# Hbridge.net
KiCad netlist of a schematic drawn in Altium Designer
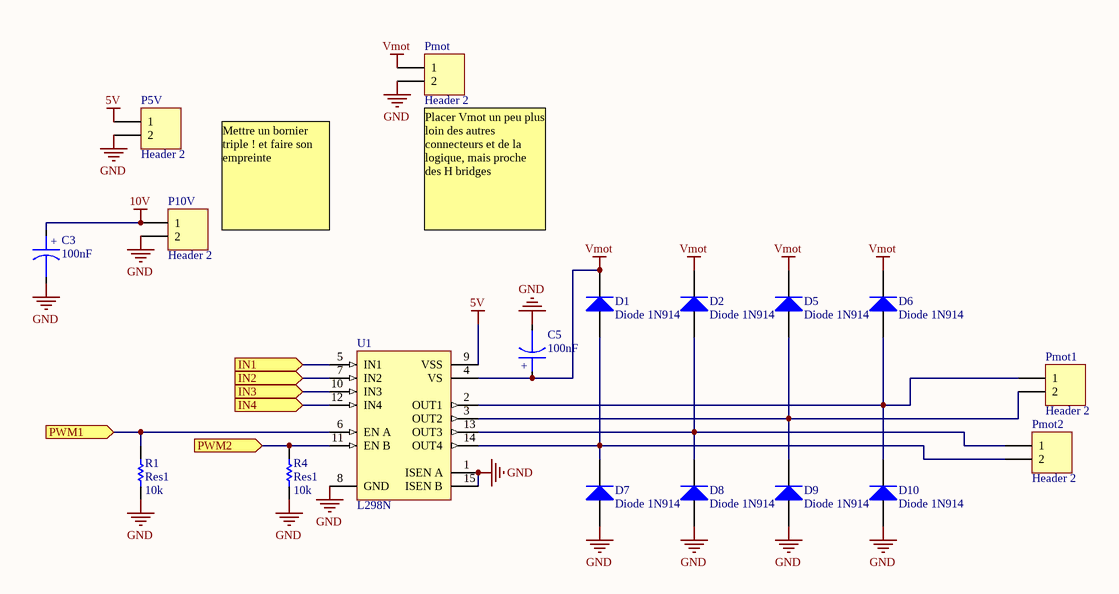
[diagram p0: Hbridge.SchDoc]

(export (version "E")
  (design (tool "Eeschema 10.0.6"))
  (components
    (comp (ref "C3")
      (value "100nF")
      (footprint "RB.1/.3")
      (description "Polarized Capacitor")
      (fields (field (name "Comment") "CAP Pol"))
      (libsource (lib "7Robot") (part "CAP Pol"))
    )
    (comp (ref "C5")
      (value "100nF")
      (footprint "RB.2/.4")
      (description "Polarized Capacitor")
      (fields (field (name "Comment") "CAP Pol"))
      (libsource (lib "7Robot") (part "CAP Pol"))
    )
    (comp (ref "D1")
      (value "Diode 1N914")
      (footprint "DO-35")
      (description "High Conductance Fast Diode")
      (fields (field (name "PUBLISHER") "Altium Limited"))
      (libsource (lib "Miscellaneous Devices") (part "Diode 1N914"))
    )
    (comp (ref "D2")
      (value "Diode 1N914")
      (footprint "DO-35")
      (description "High Conductance Fast Diode")
      (fields (field (name "PUBLISHER") "Altium Limited"))
      (libsource (lib "Miscellaneous Devices") (part "Diode 1N914"))
    )
    (comp (ref "D5")
      (value "Diode 1N914")
      (footprint "DO-35")
      (description "High Conductance Fast Diode")
      (fields (field (name "PUBLISHER") "Altium Limited"))
      (libsource (lib "Miscellaneous Devices") (part "Diode 1N914"))
    )
    (comp (ref "D6")
      (value "Diode 1N914")
      (footprint "DO-35")
      (description "High Conductance Fast Diode")
      (fields (field (name "PUBLISHER") "Altium Limited"))
      (libsource (lib "Miscellaneous Devices") (part "Diode 1N914"))
    )
    (comp (ref "D7")
      (value "Diode 1N914")
      (footprint "DO-35")
      (description "High Conductance Fast Diode")
      (fields (field (name "PUBLISHER") "Altium Limited"))
      (libsource (lib "Miscellaneous Devices") (part "Diode 1N914"))
    )
    (comp (ref "D8")
      (value "Diode 1N914")
      (footprint "DO-35")
      (description "High Conductance Fast Diode")
      (fields (field (name "PUBLISHER") "Altium Limited"))
      (libsource (lib "Miscellaneous Devices") (part "Diode 1N914"))
    )
    (comp (ref "D9")
      (value "Diode 1N914")
      (footprint "DO-35")
      (description "High Conductance Fast Diode")
      (fields (field (name "PUBLISHER") "Altium Limited"))
      (libsource (lib "Miscellaneous Devices") (part "Diode 1N914"))
    )
    (comp (ref "D10")
      (value "Diode 1N914")
      (footprint "DO-35")
      (description "High Conductance Fast Diode")
      (fields (field (name "PUBLISHER") "Altium Limited"))
      (libsource (lib "Miscellaneous Devices") (part "Diode 1N914"))
    )
    (comp (ref "P5V")
      (value "Header 2")
      (footprint "Bornier male coude 2 voies")
      (description "Header, 2-Pin")
      (fields (field (name "PUBLISHER") "Altium Limited"))
      (libsource (lib "7Robot") (part "Header 2"))
    )
    (comp (ref "P10V")
      (value "Header 2")
      (footprint "Bornier male coude 2 voies")
      (description "Header, 2-Pin")
      (fields (field (name "PUBLISHER") "Altium Limited"))
      (libsource (lib "7Robot") (part "Header 2"))
    )
    (comp (ref "Pmot")
      (value "Header 2")
      (footprint "Bornier male coude 2 voies")
      (description "Header, 2-Pin")
      (fields (field (name "PUBLISHER") "Altium Limited"))
      (libsource (lib "7Robot") (part "Header 2"))
    )
    (comp (ref "Pmot1")
      (value "Header 2")
      (footprint "TERM2W-3.5")
      (description "Header, 2-Pin")
      (fields (field (name "PUBLISHER") "Altium Limited"))
      (libsource (lib "7Robot") (part "Header 2"))
    )
    (comp (ref "Pmot2")
      (value "Header 2")
      (footprint "TERM2W-3.5")
      (description "Header, 2-Pin")
      (fields (field (name "PUBLISHER") "Altium Limited"))
      (libsource (lib "7Robot") (part "Header 2"))
    )
    (comp (ref "R1")
      (value "Res1")
      (footprint "AXIAL-0.3")
      (description "Resistor")
      (fields (field (name "ALTIUM_VALUE") "10k") (field (name "PUBLISHER") "Altium Limited"))
      (libsource (lib "Miscellaneous Devices") (part "Res1"))
    )
    (comp (ref "R4")
      (value "Res1")
      (footprint "AXIAL-0.3")
      (description "Resistor")
      (fields (field (name "ALTIUM_VALUE") "10k") (field (name "PUBLISHER") "Altium Limited"))
      (libsource (lib "Miscellaneous Devices") (part "Res1"))
    )
    (comp (ref "U1")
      (value "L298N")
      (footprint "Multiwatt15V")
      (description "Dual Full Bridge Driver")
      (fields (field (name "PUBLISHER") "Altium Limited"))
      (libsource (lib "ST Interface DC Motor Controller") (part "L298N"))
    )
  )
  (nets
    (net (code "1") (name "/IN1") (class "Default")
      (node (ref "U1") (pin "5") (pinfunction "IN1_5") (pintype "input"))
    )
    (net (code "2") (name "/IN2") (class "Default")
      (node (ref "U1") (pin "7") (pinfunction "IN2_7") (pintype "input"))
    )
    (net (code "3") (name "/IN3") (class "Default")
      (node (ref "U1") (pin "10") (pinfunction "IN3_10") (pintype "input"))
    )
    (net (code "4") (name "/IN4") (class "Default")
      (node (ref "U1") (pin "12") (pinfunction "IN4_12") (pintype "input"))
    )
    (net (code "5") (name "/PWM1") (class "Default")
      (node (ref "R1") (pin "2") (pinfunction "2_2") (pintype "passive"))
      (node (ref "U1") (pin "6") (pinfunction "EN_A_6") (pintype "input"))
    )
    (net (code "6") (name "/PWM2") (class "Default")
      (node (ref "R4") (pin "2") (pinfunction "2_2") (pintype "passive"))
      (node (ref "U1") (pin "11") (pinfunction "EN_B_11") (pintype "input"))
    )
    (net (code "7") (name "5V") (class "Default")
      (node (ref "P5V") (pin "1") (pinfunction "1_1") (pintype "passive"))
      (node (ref "U1") (pin "9") (pinfunction "VSS_9") (pintype "power_in"))
    )
    (net (code "8") (name "10V") (class "Default")
      (node (ref "C3") (pin "1") (pinfunction "1_1") (pintype "passive"))
      (node (ref "P10V") (pin "1") (pinfunction "1_1") (pintype "passive"))
    )
    (net (code "9") (name "GND") (class "Default")
      (node (ref "C3") (pin "2") (pinfunction "2_2") (pintype "passive"))
      (node (ref "C5") (pin "2") (pinfunction "2_2") (pintype "passive"))
      (node (ref "D10") (pin "1") (pinfunction "A_1") (pintype "passive"))
      (node (ref "D7") (pin "1") (pinfunction "A_1") (pintype "passive"))
      (node (ref "D8") (pin "1") (pinfunction "A_1") (pintype "passive"))
      (node (ref "D9") (pin "1") (pinfunction "A_1") (pintype "passive"))
      (node (ref "P10V") (pin "2") (pinfunction "2_2") (pintype "passive"))
      (node (ref "P5V") (pin "2") (pinfunction "2_2") (pintype "passive"))
      (node (ref "Pmot") (pin "2") (pinfunction "2_2") (pintype "passive"))
      (node (ref "R1") (pin "1") (pinfunction "1_1") (pintype "passive"))
      (node (ref "R4") (pin "1") (pinfunction "1_1") (pintype "passive"))
      (node (ref "U1") (pin "1") (pinfunction "ISEN_A_1") (pintype "passive"))
      (node (ref "U1") (pin "15") (pinfunction "ISEN_B_15") (pintype "passive"))
      (node (ref "U1") (pin "8") (pinfunction "GND_8") (pintype "power_in"))
    )
    (net (code "10") (name "Net-(D1-A)") (class "Default")
      (node (ref "D1") (pin "1") (pinfunction "A_1") (pintype "passive"))
      (node (ref "D7") (pin "2") (pinfunction "K_2") (pintype "passive"))
      (node (ref "Pmot2") (pin "2") (pinfunction "2_2") (pintype "passive"))
      (node (ref "U1") (pin "14") (pinfunction "OUT4_14") (pintype "output"))
    )
    (net (code "11") (name "Net-(D2-A)") (class "Default")
      (node (ref "D2") (pin "1") (pinfunction "A_1") (pintype "passive"))
      (node (ref "D8") (pin "2") (pinfunction "K_2") (pintype "passive"))
      (node (ref "Pmot2") (pin "1") (pinfunction "1_1") (pintype "passive"))
      (node (ref "U1") (pin "13") (pinfunction "OUT3_13") (pintype "output"))
    )
    (net (code "12") (name "Net-(D5-A)") (class "Default")
      (node (ref "D5") (pin "1") (pinfunction "A_1") (pintype "passive"))
      (node (ref "D9") (pin "2") (pinfunction "K_2") (pintype "passive"))
      (node (ref "Pmot1") (pin "2") (pinfunction "2_2") (pintype "passive"))
      (node (ref "U1") (pin "3") (pinfunction "OUT2_3") (pintype "output"))
    )
    (net (code "13") (name "Net-(D10-K)") (class "Default")
      (node (ref "D10") (pin "2") (pinfunction "K_2") (pintype "passive"))
      (node (ref "D6") (pin "1") (pinfunction "A_1") (pintype "passive"))
      (node (ref "Pmot1") (pin "1") (pinfunction "1_1") (pintype "passive"))
      (node (ref "U1") (pin "2") (pinfunction "OUT1_2") (pintype "output"))
    )
    (net (code "14") (name "Vmot") (class "Default")
      (node (ref "C5") (pin "1") (pinfunction "1_1") (pintype "passive"))
      (node (ref "D1") (pin "2") (pinfunction "K_2") (pintype "passive"))
      (node (ref "D2") (pin "2") (pinfunction "K_2") (pintype "passive"))
      (node (ref "D5") (pin "2") (pinfunction "K_2") (pintype "passive"))
      (node (ref "D6") (pin "2") (pinfunction "K_2") (pintype "passive"))
      (node (ref "Pmot") (pin "1") (pinfunction "1_1") (pintype "passive"))
      (node (ref "U1") (pin "4") (pinfunction "VS_4") (pintype "power_in"))
    )
  )
)
